# SCH_PCB_2026-08-12.net
KiCad netlist of a schematic drawn in EasyEDA
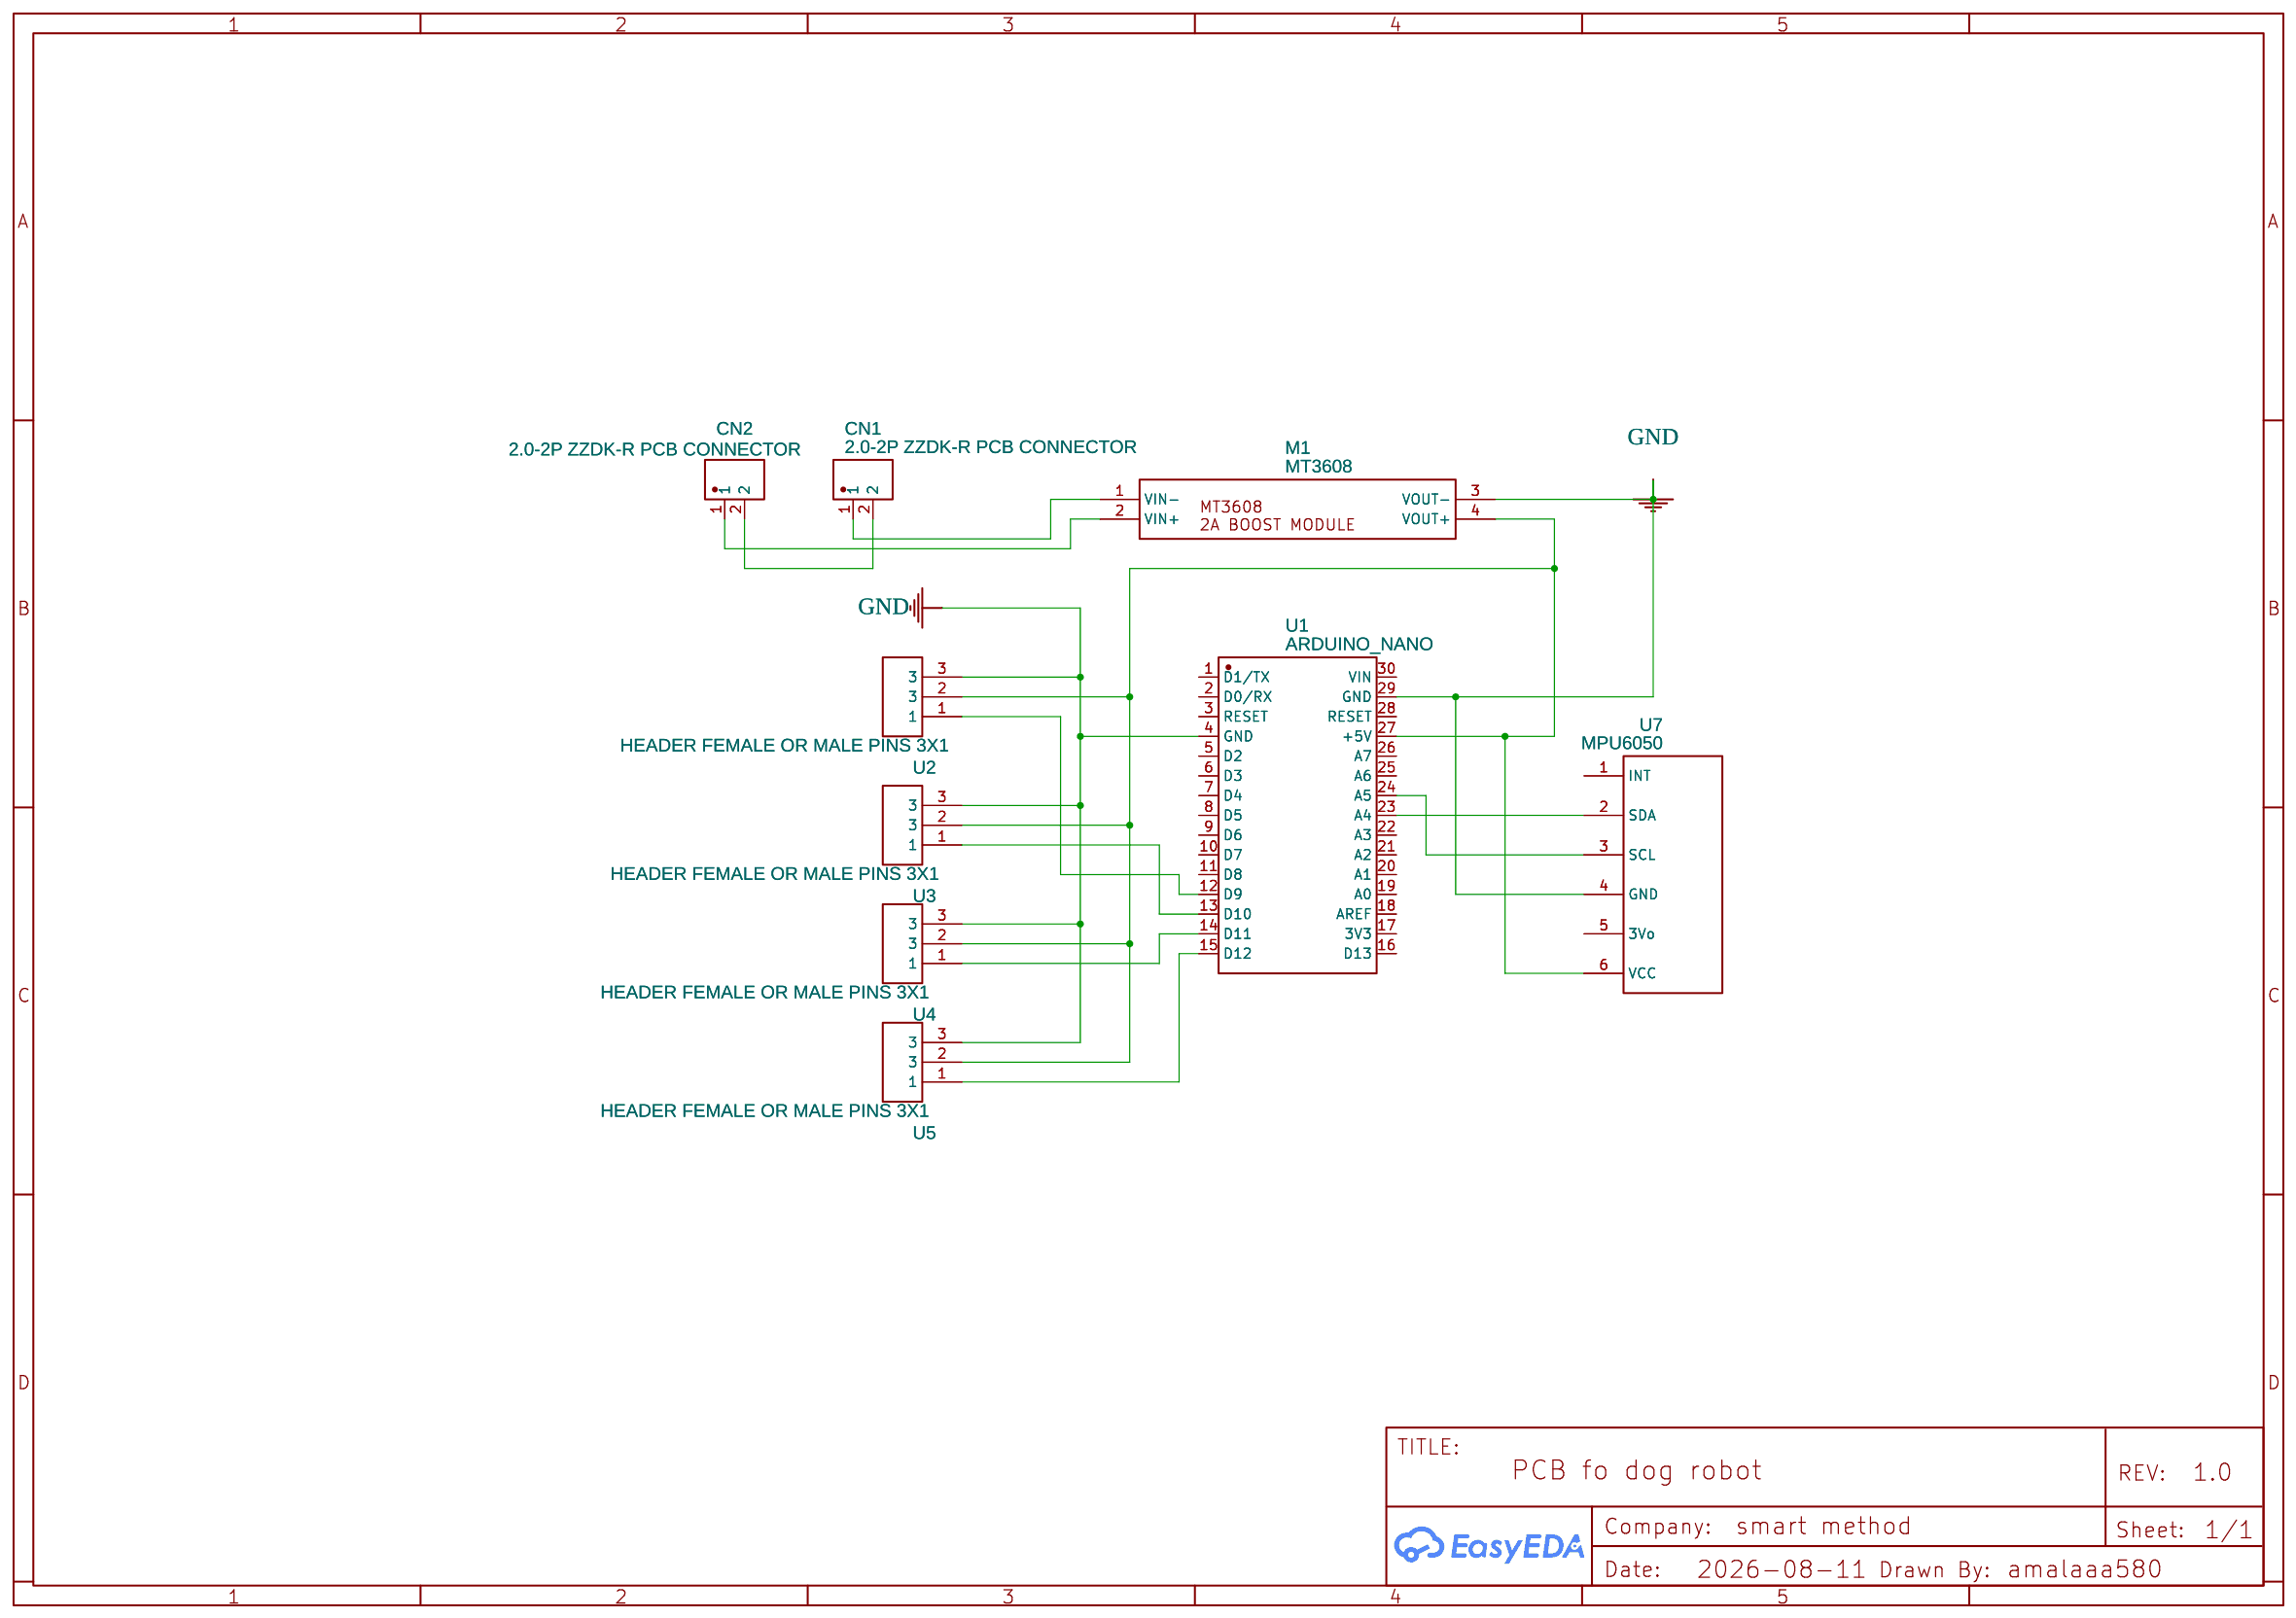
[diagram p0: schematic sheet]

(export (version "E")
  (design (tool "Eeschema 10.0.6"))
  (components
    (comp (ref "CN1")
      (value "2.0-2P ZZDK-R PCB CONNECTOR")
      (fields
        (field (name "Manufacturer Part") "2.0-2P ZZDK-R PCB Connector")
        (field (name "Manufacturer") "SHOU HAN(首韩)")
      )
      (libsource (lib "") (part "2.0-2P ZZDK-R PCB CONNECTOR"))
    )
    (comp (ref "CN2")
      (value "2.0-2P ZZDK-R PCB CONNECTOR")
      (fields
        (field (name "Manufacturer Part") "2.0-2P ZZDK-R PCB Connector")
        (field (name "Manufacturer") "SHOU HAN(首韩)")
      )
      (libsource (lib "") (part "2.0-2P ZZDK-R PCB CONNECTOR"))
    )
    (comp (ref "M1") (value "MT3608") (libsource (lib "") (part "MT3608")))
    (comp (ref "U1") (value "ARDUINO_NANO") (libsource (lib "") (part "ARDUINO_NANO")))
    (comp (ref "U2")
      (value "HEADER FEMALE OR MALE PINS 3X1")
      (libsource (lib "") (part "HEADER FEMALE OR MALE PINS 3X1"))
    )
    (comp (ref "U3")
      (value "HEADER FEMALE OR MALE PINS 3X1")
      (libsource (lib "") (part "HEADER FEMALE OR MALE PINS 3X1"))
    )
    (comp (ref "U4")
      (value "HEADER FEMALE OR MALE PINS 3X1")
      (libsource (lib "") (part "HEADER FEMALE OR MALE PINS 3X1"))
    )
    (comp (ref "U5")
      (value "HEADER FEMALE OR MALE PINS 3X1")
      (libsource (lib "") (part "HEADER FEMALE OR MALE PINS 3X1"))
    )
    (comp (ref "U7") (value "MPU6050") (libsource (lib "") (part "MPU6050")))
  )
  (nets
    (net (code "1") (name "GND") (class "Default")
      (node (ref "M1") (pin "3") (pinfunction "VOUT-_3") (pintype "unspecified"))
      (node (ref "U1") (pin "29") (pinfunction "GND_29") (pintype "unspecified"))
      (node (ref "U1") (pin "4") (pinfunction "GND_4") (pintype "unspecified"))
      (node (ref "U2") (pin "3") (pinfunction "3_3") (pintype "unspecified"))
      (node (ref "U3") (pin "3") (pinfunction "3_3") (pintype "unspecified"))
      (node (ref "U4") (pin "3") (pinfunction "3_3") (pintype "unspecified"))
      (node (ref "U5") (pin "3") (pinfunction "3_3") (pintype "unspecified"))
      (node (ref "U7") (pin "4") (pinfunction "GND_4") (pintype "unspecified"))
    )
    (net (code "2") (name "Net-(CN1-Pad2)") (class "Default")
      (node (ref "CN1") (pin "2") (pinfunction "2_2") (pintype "unspecified"))
      (node (ref "CN2") (pin "2") (pinfunction "2_2") (pintype "unspecified"))
    )
    (net (code "3") (name "Net-(M1-VIN+)") (class "Default")
      (node (ref "CN2") (pin "1") (pinfunction "1_1") (pintype "unspecified"))
      (node (ref "M1") (pin "2") (pinfunction "VIN+_2") (pintype "unspecified"))
    )
    (net (code "4") (name "Net-(M1-VIN-)") (class "Default")
      (node (ref "CN1") (pin "1") (pinfunction "1_1") (pintype "unspecified"))
      (node (ref "M1") (pin "1") (pinfunction "VIN-_1") (pintype "unspecified"))
    )
    (net (code "5") (name "Net-(M1-VOUT+)") (class "Default")
      (node (ref "M1") (pin "4") (pinfunction "VOUT+_4") (pintype "unspecified"))
      (node (ref "U1") (pin "27") (pinfunction "+5V_27") (pintype "unspecified"))
      (node (ref "U2") (pin "2") (pinfunction "3_2") (pintype "unspecified"))
      (node (ref "U3") (pin "2") (pinfunction "3_2") (pintype "unspecified"))
      (node (ref "U4") (pin "2") (pinfunction "3_2") (pintype "unspecified"))
      (node (ref "U5") (pin "2") (pinfunction "3_2") (pintype "unspecified"))
      (node (ref "U7") (pin "6") (pinfunction "VCC_6") (pintype "unspecified"))
    )
    (net (code "6") (name "Net-(U1-A4)") (class "Default")
      (node (ref "U1") (pin "23") (pinfunction "A4_23") (pintype "unspecified"))
      (node (ref "U7") (pin "2") (pinfunction "SDA_2") (pintype "unspecified"))
    )
    (net (code "7") (name "Net-(U1-A5)") (class "Default")
      (node (ref "U1") (pin "24") (pinfunction "A5_24") (pintype "unspecified"))
      (node (ref "U7") (pin "3") (pinfunction "SCL_3") (pintype "unspecified"))
    )
    (net (code "8") (name "Net-(U1-D9)") (class "Default")
      (node (ref "U1") (pin "12") (pinfunction "D9_12") (pintype "unspecified"))
      (node (ref "U2") (pin "1") (pinfunction "1_1") (pintype "unspecified"))
    )
    (net (code "9") (name "Net-(U1-D10)") (class "Default")
      (node (ref "U1") (pin "13") (pinfunction "D10_13") (pintype "unspecified"))
      (node (ref "U3") (pin "1") (pinfunction "1_1") (pintype "unspecified"))
    )
    (net (code "10") (name "Net-(U1-D11)") (class "Default")
      (node (ref "U1") (pin "14") (pinfunction "D11_14") (pintype "unspecified"))
      (node (ref "U4") (pin "1") (pinfunction "1_1") (pintype "unspecified"))
    )
    (net (code "11") (name "Net-(U1-D12)") (class "Default")
      (node (ref "U1") (pin "15") (pinfunction "D12_15") (pintype "unspecified"))
      (node (ref "U5") (pin "1") (pinfunction "1_1") (pintype "unspecified"))
    )
    (net (code "12") (name "unconnected-(U1-3V3-Pad17)") (class "Default")
      (node (ref "U1") (pin "17") (pinfunction "3V3_17") (pintype "unspecified"))
    )
    (net (code "13") (name "unconnected-(U1-A0-Pad19)") (class "Default")
      (node (ref "U1") (pin "19") (pinfunction "A0_19") (pintype "unspecified"))
    )
    (net (code "14") (name "unconnected-(U1-A1-Pad20)") (class "Default")
      (node (ref "U1") (pin "20") (pinfunction "A1_20") (pintype "unspecified"))
    )
    (net (code "15") (name "unconnected-(U1-A2-Pad21)") (class "Default")
      (node (ref "U1") (pin "21") (pinfunction "A2_21") (pintype "unspecified"))
    )
    (net (code "16") (name "unconnected-(U1-A3-Pad22)") (class "Default")
      (node (ref "U1") (pin "22") (pinfunction "A3_22") (pintype "unspecified"))
    )
    (net (code "17") (name "unconnected-(U1-A6-Pad25)") (class "Default")
      (node (ref "U1") (pin "25") (pinfunction "A6_25") (pintype "unspecified"))
    )
    (net (code "18") (name "unconnected-(U1-A7-Pad26)") (class "Default")
      (node (ref "U1") (pin "26") (pinfunction "A7_26") (pintype "unspecified"))
    )
    (net (code "19") (name "unconnected-(U1-AREF-Pad18)") (class "Default")
      (node (ref "U1") (pin "18") (pinfunction "AREF_18") (pintype "unspecified"))
    )
    (net (code "20") (name "unconnected-(U1-D0{slash}RX-Pad2)") (class "Default")
      (node (ref "U1") (pin "2") (pinfunction "D0/RX_2") (pintype "unspecified"))
    )
    (net (code "21") (name "unconnected-(U1-D1{slash}TX-Pad1)") (class "Default")
      (node (ref "U1") (pin "1") (pinfunction "D1/TX_1") (pintype "unspecified"))
    )
    (net (code "22") (name "unconnected-(U1-D2-Pad5)") (class "Default")
      (node (ref "U1") (pin "5") (pinfunction "D2_5") (pintype "unspecified"))
    )
    (net (code "23") (name "unconnected-(U1-D3-Pad6)") (class "Default")
      (node (ref "U1") (pin "6") (pinfunction "D3_6") (pintype "unspecified"))
    )
    (net (code "24") (name "unconnected-(U1-D4-Pad7)") (class "Default")
      (node (ref "U1") (pin "7") (pinfunction "D4_7") (pintype "unspecified"))
    )
    (net (code "25") (name "unconnected-(U1-D5-Pad8)") (class "Default")
      (node (ref "U1") (pin "8") (pinfunction "D5_8") (pintype "unspecified"))
    )
    (net (code "26") (name "unconnected-(U1-D6-Pad9)") (class "Default")
      (node (ref "U1") (pin "9") (pinfunction "D6_9") (pintype "unspecified"))
    )
    (net (code "27") (name "unconnected-(U1-D7-Pad10)") (class "Default")
      (node (ref "U1") (pin "10") (pinfunction "D7_10") (pintype "unspecified"))
    )
    (net (code "28") (name "unconnected-(U1-D8-Pad11)") (class "Default")
      (node (ref "U1") (pin "11") (pinfunction "D8_11") (pintype "unspecified"))
    )
    (net (code "29") (name "unconnected-(U1-D13-Pad16)") (class "Default")
      (node (ref "U1") (pin "16") (pinfunction "D13_16") (pintype "unspecified"))
    )
    (net (code "30") (name "unconnected-(U1-RESET-Pad3)") (class "Default")
      (node (ref "U1") (pin "3") (pinfunction "RESET_3") (pintype "unspecified"))
    )
    (net (code "31") (name "unconnected-(U1-RESET-Pad28)") (class "Default")
      (node (ref "U1") (pin "28") (pinfunction "RESET_28") (pintype "unspecified"))
    )
    (net (code "32") (name "unconnected-(U1-VIN-Pad30)") (class "Default")
      (node (ref "U1") (pin "30") (pinfunction "VIN_30") (pintype "unspecified"))
    )
    (net (code "33") (name "unconnected-(U7-3Vo-Pad5)") (class "Default")
      (node (ref "U7") (pin "5") (pinfunction "3Vo_5") (pintype "unspecified"))
    )
    (net (code "34") (name "unconnected-(U7-INT-Pad1)") (class "Default")
      (node (ref "U7") (pin "1") (pinfunction "INT_1") (pintype "unspecified"))
    )
  )
)
